# sst_ur_01.net
KiCad netlist of a schematic drawn in EAGLE
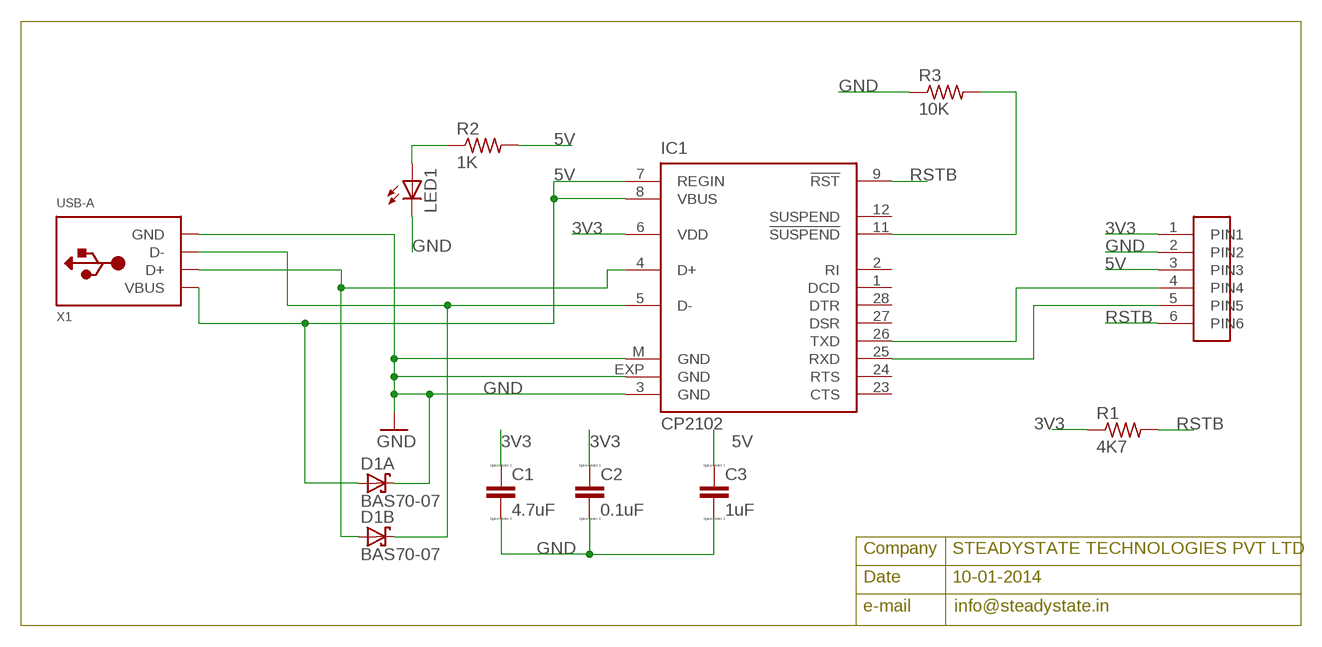
[diagram p0: schematic, sheet 1]

(export (version "E")
  (design (tool "Eeschema 10.0.6"))
  (components
    (comp (ref "C1")
      (value "4.7uF")
      (footprint "eagle-import:C3216")
      (libsource (lib "eagle-import") (part "CC3216"))
    )
    (comp (ref "C2")
      (value "0.1uF")
      (footprint "eagle-import:C1206")
      (libsource (lib "eagle-import") (part "CC1206"))
    )
    (comp (ref "C3")
      (value "1uF")
      (footprint "eagle-import:C1206")
      (libsource (lib "eagle-import") (part "CC1206"))
    )
    (comp (ref "D1")
      (value "BAS70-07")
      (footprint "eagle-import:SOT143-R")
      (libsource (lib "eagle-import") (part "BAS70-07"))
    )
    (comp (ref "IC1")
      (value "CP2102")
      (footprint "eagle-import:MLP28")
      (fields (field (name "MF") "FARNELL") (field (name "MPN") "CP2102-GM"))
      (libsource (lib "eagle-import") (part "CP2102"))
    )
    (comp (ref "LED1")
      (value "LEDCHIPLED_1206")
      (footprint "eagle-import:CHIPLED_1206")
      (libsource (lib "eagle-import") (part "LEDCHIPLED_1206"))
    )
    (comp (ref "R1")
      (value "4K7")
      (footprint "eagle-import:R1210")
      (libsource (lib "eagle-import") (part "R-US_R1210"))
    )
    (comp (ref "R2")
      (value "1K")
      (footprint "eagle-import:R1210")
      (libsource (lib "eagle-import") (part "R-US_R1210"))
    )
    (comp (ref "R3")
      (value "10K")
      (footprint "eagle-import:R1210")
      (libsource (lib "eagle-import") (part "R-US_R1210"))
    )
    (comp (ref "U$1")
      (value "SIL6")
      (footprint "eagle-import:SIL6")
      (libsource (lib "eagle-import") (part "SIL6"))
    )
    (comp (ref "X1")
      (value "USB-A")
      (footprint "eagle-import:MOLEX_480371000")
      (libsource (lib "eagle-import") (part "USB-A"))
    )
  )
  (nets
    (net (code "1") (name "/3V3") (class "Default")
      (node (ref "C1") (pin "1") (pinfunction "1_1") (pintype "passive"))
      (node (ref "C2") (pin "1") (pinfunction "1_1") (pintype "passive"))
      (node (ref "IC1") (pin "6") (pinfunction "VDD_6") (pintype "power_in"))
      (node (ref "R1") (pin "1") (pinfunction "1_1") (pintype "passive"))
      (node (ref "U$1") (pin "1") (pinfunction "PIN1_1") (pintype "bidirectional"))
    )
    (net (code "2") (name "/5V") (class "Default")
      (node (ref "C3") (pin "1") (pinfunction "1_1") (pintype "passive"))
      (node (ref "D1") (pin "4") (pinfunction "A_4") (pintype "passive"))
      (node (ref "IC1") (pin "7") (pinfunction "REGIN_7") (pintype "passive"))
      (node (ref "IC1") (pin "8") (pinfunction "VBUS_8") (pintype "input"))
      (node (ref "R2") (pin "2") (pinfunction "2_2") (pintype "passive"))
      (node (ref "U$1") (pin "3") (pinfunction "PIN3_3") (pintype "bidirectional"))
      (node (ref "X1") (pin "1") (pinfunction "VBUS_1") (pintype "power_in"))
    )
    (net (code "3") (name "/RSTB") (class "Default")
      (node (ref "IC1") (pin "9") (pinfunction "~{RST}_9") (pintype "bidirectional"))
      (node (ref "R1") (pin "2") (pinfunction "2_2") (pintype "passive"))
      (node (ref "U$1") (pin "6") (pinfunction "PIN6_6") (pintype "bidirectional"))
    )
    (net (code "4") (name "GND") (class "Default")
      (node (ref "C1") (pin "2") (pinfunction "2_2") (pintype "passive"))
      (node (ref "C2") (pin "2") (pinfunction "2_2") (pintype "passive"))
      (node (ref "C3") (pin "2") (pinfunction "2_2") (pintype "passive"))
      (node (ref "D1") (pin "1") (pinfunction "C_1") (pintype "passive"))
      (node (ref "IC1") (pin "3") (pinfunction "GND_3") (pintype "power_in"))
      (node (ref "IC1") (pin "EXP") (pinfunction "GND_EXP") (pintype "power_in"))
      (node (ref "IC1") (pin "M") (pinfunction "GND_M") (pintype "power_in"))
      (node (ref "LED1") (pin "C") (pinfunction "C_C") (pintype "passive"))
      (node (ref "R3") (pin "1") (pinfunction "1_1") (pintype "passive"))
      (node (ref "U$1") (pin "2") (pinfunction "PIN2_2") (pintype "bidirectional"))
      (node (ref "X1") (pin "4") (pinfunction "GND_4") (pintype "power_in"))
    )
    (net (code "5") (name "Net-(D1B-A)") (class "Default")
      (node (ref "D1") (pin "3") (pinfunction "A_3") (pintype "passive"))
      (node (ref "IC1") (pin "4") (pinfunction "D+_4") (pintype "bidirectional"))
      (node (ref "X1") (pin "3") (pinfunction "D+_3") (pintype "bidirectional"))
    )
    (net (code "6") (name "Net-(D1B-C)") (class "Default")
      (node (ref "D1") (pin "2") (pinfunction "C_2") (pintype "passive"))
      (node (ref "IC1") (pin "5") (pinfunction "D-_5") (pintype "bidirectional"))
      (node (ref "X1") (pin "2") (pinfunction "D-_2") (pintype "bidirectional"))
    )
    (net (code "7") (name "Net-(IC1-RXD)") (class "Default")
      (node (ref "IC1") (pin "25") (pinfunction "RXD_25") (pintype "input"))
      (node (ref "U$1") (pin "5") (pinfunction "PIN5_5") (pintype "bidirectional"))
    )
    (net (code "8") (name "Net-(IC1-TXD)") (class "Default")
      (node (ref "IC1") (pin "26") (pinfunction "TXD_26") (pintype "output"))
      (node (ref "U$1") (pin "4") (pinfunction "PIN4_4") (pintype "bidirectional"))
    )
    (net (code "9") (name "Net-(IC1-~{SUSPEND})") (class "Default")
      (node (ref "IC1") (pin "11") (pinfunction "~{SUSPEND}_11") (pintype "output"))
      (node (ref "R3") (pin "2") (pinfunction "2_2") (pintype "passive"))
    )
    (net (code "10") (name "Net-(LED1-PadA)") (class "Default")
      (node (ref "LED1") (pin "A") (pinfunction "A_A") (pintype "passive"))
      (node (ref "R2") (pin "1") (pinfunction "1_1") (pintype "passive"))
    )
    (net (code "11") (name "unconnected-(IC1-CTS-Pad23)") (class "Default")
      (node (ref "IC1") (pin "23") (pinfunction "CTS_23") (pintype "input"))
    )
    (net (code "12") (name "unconnected-(IC1-DCD-Pad1)") (class "Default")
      (node (ref "IC1") (pin "1") (pinfunction "DCD_1") (pintype "input"))
    )
    (net (code "13") (name "unconnected-(IC1-DSR-Pad27)") (class "Default")
      (node (ref "IC1") (pin "27") (pinfunction "DSR_27") (pintype "input"))
    )
    (net (code "14") (name "unconnected-(IC1-DTR-Pad28)") (class "Default")
      (node (ref "IC1") (pin "28") (pinfunction "DTR_28") (pintype "output"))
    )
    (net (code "15") (name "unconnected-(IC1-RI-Pad2)") (class "Default")
      (node (ref "IC1") (pin "2") (pinfunction "RI_2") (pintype "input"))
    )
    (net (code "16") (name "unconnected-(IC1-RTS-Pad24)") (class "Default")
      (node (ref "IC1") (pin "24") (pinfunction "RTS_24") (pintype "output"))
    )
    (net (code "17") (name "unconnected-(IC1-SUSPEND-Pad12)") (class "Default")
      (node (ref "IC1") (pin "12") (pinfunction "SUSPEND_12") (pintype "output"))
    )
  )
)
